# 04pwr_pmic.net
KiCad netlist of a schematic drawn in Altium Designer
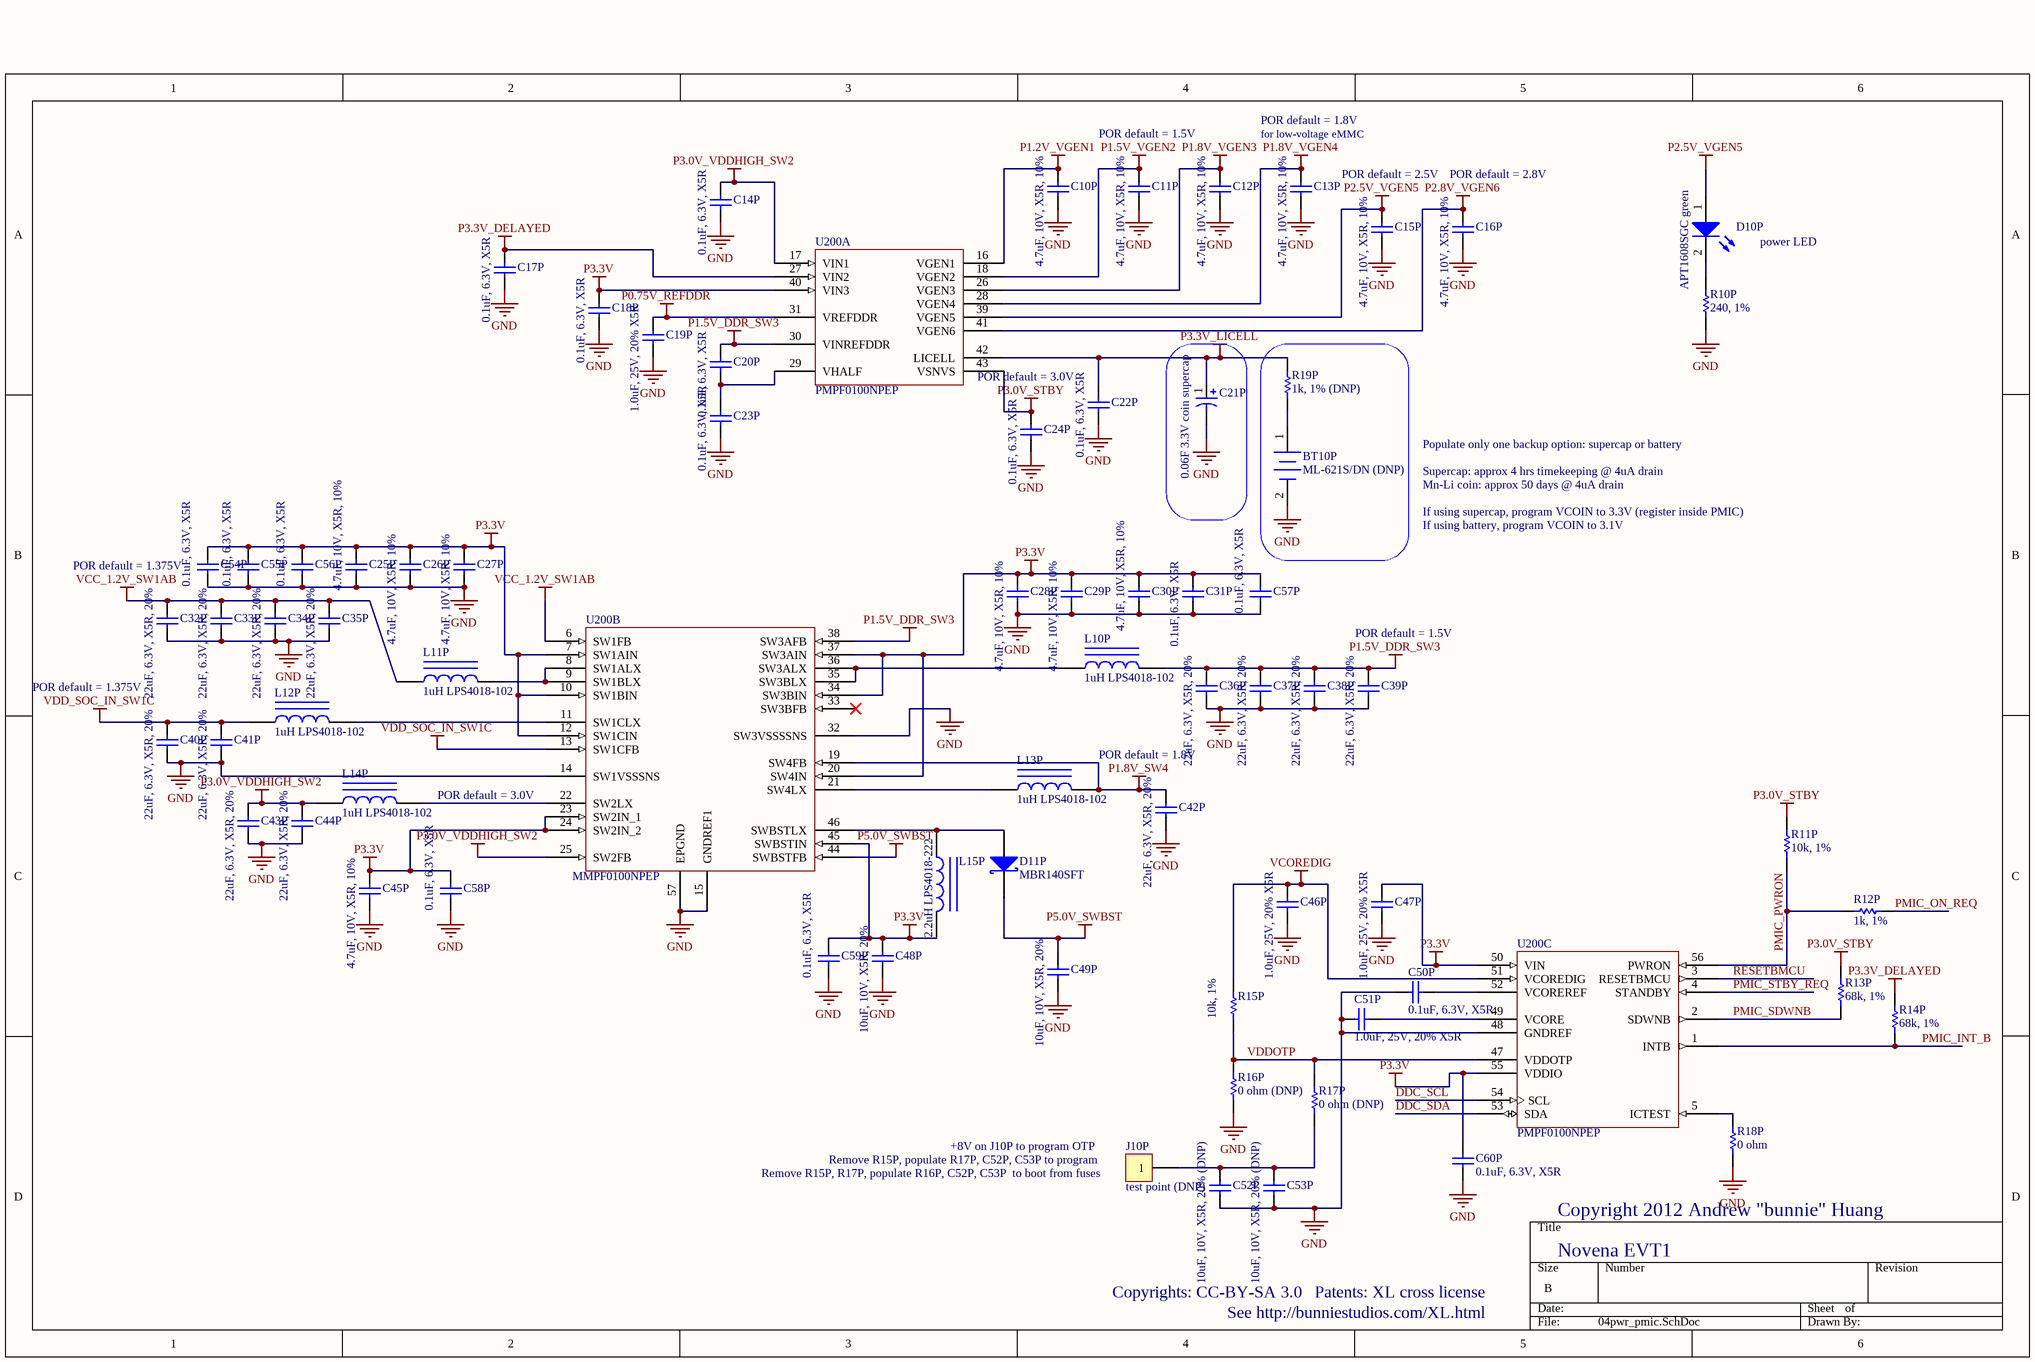
[diagram p0: 04pwr_pmic.SchDoc]

(export (version "E")
  (design (tool "Eeschema 10.0.6"))
  (components
    (comp (ref "BT10P")
      (value "ML-621S/DN (DNP)")
      (footprint "PAN_ML-621S-DN")
      (description "Panasonic Manganese Lithium Rechargeable battery")
      (fields (field (name "PUBLISHER") "Altium Limited"))
      (libsource (lib "Miscellaneous Devices") (part "Battery"))
    )
    (comp (ref "C10P")
      (value "4.7uF, 10V, X5R, 10%")
      (footprint "CAPC1608N_HD")
      (description "Capacitor (Semiconductor SIM Model)")
      (fields (field (name "PUBLISHER") "Altium Limited"))
      (libsource (lib "Miscellaneous Devices") (part "Cap Semi"))
    )
    (comp (ref "C11P")
      (value "4.7uF, 10V, X5R, 10%")
      (footprint "CAPC1608N_HD")
      (description "Capacitor (Semiconductor SIM Model)")
      (fields (field (name "PUBLISHER") "Altium Limited"))
      (libsource (lib "Miscellaneous Devices") (part "Cap Semi"))
    )
    (comp (ref "C12P")
      (value "4.7uF, 10V, X5R, 10%")
      (footprint "CAPC1608N_HD")
      (description "Capacitor (Semiconductor SIM Model)")
      (fields (field (name "PUBLISHER") "Altium Limited"))
      (libsource (lib "Miscellaneous Devices") (part "Cap Semi"))
    )
    (comp (ref "C13P")
      (value "4.7uF, 10V, X5R, 10%")
      (footprint "CAPC1608N_HD")
      (description "Capacitor (Semiconductor SIM Model)")
      (fields (field (name "PUBLISHER") "Altium Limited"))
      (libsource (lib "Miscellaneous Devices") (part "Cap Semi"))
    )
    (comp (ref "C14P")
      (value "0.1uF, 6.3V, X5R")
      (footprint "CAPC0603N_B")
      (description "Capacitor (Semiconductor SIM Model)")
      (fields (field (name "PUBLISHER") "Altium Limited"))
      (libsource (lib "Miscellaneous Devices") (part "Cap Semi"))
    )
    (comp (ref "C15P")
      (value "4.7uF, 10V, X5R, 10%")
      (footprint "CAPC1608N_HD")
      (description "Capacitor (Semiconductor SIM Model)")
      (fields (field (name "PUBLISHER") "Altium Limited"))
      (libsource (lib "Miscellaneous Devices") (part "Cap Semi"))
    )
    (comp (ref "C16P")
      (value "4.7uF, 10V, X5R, 10%")
      (footprint "CAPC1608N_HD")
      (description "Capacitor (Semiconductor SIM Model)")
      (fields (field (name "PUBLISHER") "Altium Limited"))
      (libsource (lib "Miscellaneous Devices") (part "Cap Semi"))
    )
    (comp (ref "C17P")
      (value "0.1uF, 6.3V, X5R")
      (footprint "CAPC0603N_B")
      (description "Capacitor (Semiconductor SIM Model)")
      (fields (field (name "PUBLISHER") "Altium Limited"))
      (libsource (lib "Miscellaneous Devices") (part "Cap Semi"))
    )
    (comp (ref "C18P")
      (value "0.1uF, 6.3V, X5R")
      (footprint "CAPC0603N_B")
      (description "Capacitor (Semiconductor SIM Model)")
      (fields (field (name "PUBLISHER") "Altium Limited"))
      (libsource (lib "Miscellaneous Devices") (part "Cap Semi"))
    )
    (comp (ref "C19P")
      (value "1.0uF, 25V, 20% X5R")
      (footprint "CAPC1608N_HD")
      (description "Capacitor (Semiconductor SIM Model)")
      (fields (field (name "PUBLISHER") "Altium Limited"))
      (libsource (lib "Miscellaneous Devices") (part "Cap Semi"))
    )
    (comp (ref "C20P")
      (value "0.1uF, 6.3V, X5R")
      (footprint "CAPC0603N_B")
      (description "Capacitor (Semiconductor SIM Model)")
      (fields (field (name "PUBLISHER") "Altium Limited"))
      (libsource (lib "Miscellaneous Devices") (part "Cap Semi"))
    )
    (comp (ref "C21P")
      (value "0.06F 3.3V coin supercap")
      (footprint "TAIYO_YUDEN_PAS414HR-VA5R")
      (description "Taiyo Yuden PAS414HR-VA5R")
      (fields (field (name "PUBLISHER") "Altium Limited"))
      (libsource (lib "Miscellaneous Devices") (part "Cap Pol3"))
    )
    (comp (ref "C22P")
      (value "0.1uF, 6.3V, X5R")
      (footprint "CAPC0603N_B")
      (description "Capacitor (Semiconductor SIM Model)")
      (fields (field (name "PUBLISHER") "Altium Limited"))
      (libsource (lib "Miscellaneous Devices") (part "Cap Semi"))
    )
    (comp (ref "C23P")
      (value "0.1uF, 6.3V, X5R")
      (footprint "CAPC0603N_B")
      (description "Capacitor (Semiconductor SIM Model)")
      (fields (field (name "PUBLISHER") "Altium Limited"))
      (libsource (lib "Miscellaneous Devices") (part "Cap Semi"))
    )
    (comp (ref "C24P")
      (value "0.1uF, 6.3V, X5R")
      (footprint "CAPC0603N_B")
      (description "Capacitor (Semiconductor SIM Model)")
      (fields (field (name "PUBLISHER") "Altium Limited"))
      (libsource (lib "Miscellaneous Devices") (part "Cap Semi"))
    )
    (comp (ref "C25P")
      (value "4.7uF, 10V, X5R, 10%")
      (footprint "CAPC1608N_HD")
      (description "Capacitor (Semiconductor SIM Model)")
      (fields (field (name "PUBLISHER") "Altium Limited"))
      (libsource (lib "Miscellaneous Devices") (part "Cap Semi"))
    )
    (comp (ref "C26P")
      (value "4.7uF, 10V, X5R, 10%")
      (footprint "CAPC1608N_HD")
      (description "Capacitor (Semiconductor SIM Model)")
      (fields (field (name "PUBLISHER") "Altium Limited"))
      (libsource (lib "Miscellaneous Devices") (part "Cap Semi"))
    )
    (comp (ref "C27P")
      (value "4.7uF, 10V, X5R, 10%")
      (footprint "CAPC1608N_HD")
      (description "Capacitor (Semiconductor SIM Model)")
      (fields (field (name "PUBLISHER") "Altium Limited"))
      (libsource (lib "Miscellaneous Devices") (part "Cap Semi"))
    )
    (comp (ref "C28P")
      (value "4.7uF, 10V, X5R, 10%")
      (footprint "CAPC1608N_HD")
      (description "Capacitor (Semiconductor SIM Model)")
      (fields (field (name "PUBLISHER") "Altium Limited"))
      (libsource (lib "Miscellaneous Devices") (part "Cap Semi"))
    )
    (comp (ref "C29P")
      (value "4.7uF, 10V, X5R, 10%")
      (footprint "CAPC1608N_HD")
      (description "Capacitor (Semiconductor SIM Model)")
      (fields (field (name "PUBLISHER") "Altium Limited"))
      (libsource (lib "Miscellaneous Devices") (part "Cap Semi"))
    )
    (comp (ref "C30P")
      (value "4.7uF, 10V, X5R, 10%")
      (footprint "CAPC1608N_HD")
      (description "Capacitor (Semiconductor SIM Model)")
      (fields (field (name "PUBLISHER") "Altium Limited"))
      (libsource (lib "Miscellaneous Devices") (part "Cap Semi"))
    )
    (comp (ref "C31P")
      (value "0.1uF, 6.3V, X5R")
      (footprint "CAPC0603N_B")
      (description "Capacitor (Semiconductor SIM Model)")
      (fields (field (name "PUBLISHER") "Altium Limited"))
      (libsource (lib "Miscellaneous Devices") (part "Cap Semi"))
    )
    (comp (ref "C32P")
      (value "22uF, 6.3V, X5R, 20%")
      (footprint "CAPC1608N_HD")
      (description "Capacitor (Semiconductor SIM Model)")
      (fields (field (name "PUBLISHER") "Altium Limited"))
      (libsource (lib "Miscellaneous Devices") (part "Cap Semi"))
    )
    (comp (ref "C33P")
      (value "22uF, 6.3V, X5R, 20%")
      (footprint "CAPC1608N_HD")
      (description "Capacitor (Semiconductor SIM Model)")
      (fields (field (name "PUBLISHER") "Altium Limited"))
      (libsource (lib "Miscellaneous Devices") (part "Cap Semi"))
    )
    (comp (ref "C34P")
      (value "22uF, 6.3V, X5R, 20%")
      (footprint "CAPC1608N_HD")
      (description "Capacitor (Semiconductor SIM Model)")
      (fields (field (name "PUBLISHER") "Altium Limited"))
      (libsource (lib "Miscellaneous Devices") (part "Cap Semi"))
    )
    (comp (ref "C35P")
      (value "22uF, 6.3V, X5R, 20%")
      (footprint "CAPC1608N_HD")
      (description "Capacitor (Semiconductor SIM Model)")
      (fields (field (name "PUBLISHER") "Altium Limited"))
      (libsource (lib "Miscellaneous Devices") (part "Cap Semi"))
    )
    (comp (ref "C36P")
      (value "22uF, 6.3V, X5R, 20%")
      (footprint "CAPC1608N_HD")
      (description "Capacitor (Semiconductor SIM Model)")
      (fields (field (name "PUBLISHER") "Altium Limited"))
      (libsource (lib "Miscellaneous Devices") (part "Cap Semi"))
    )
    (comp (ref "C37P")
      (value "22uF, 6.3V, X5R, 20%")
      (footprint "CAPC1608N_HD")
      (description "Capacitor (Semiconductor SIM Model)")
      (fields (field (name "PUBLISHER") "Altium Limited"))
      (libsource (lib "Miscellaneous Devices") (part "Cap Semi"))
    )
    (comp (ref "C38P")
      (value "22uF, 6.3V, X5R, 20%")
      (footprint "CAPC1608N_HD")
      (description "Capacitor (Semiconductor SIM Model)")
      (fields (field (name "PUBLISHER") "Altium Limited"))
      (libsource (lib "Miscellaneous Devices") (part "Cap Semi"))
    )
    (comp (ref "C39P")
      (value "22uF, 6.3V, X5R, 20%")
      (footprint "CAPC1608N_HD")
      (description "Capacitor (Semiconductor SIM Model)")
      (fields (field (name "PUBLISHER") "Altium Limited"))
      (libsource (lib "Miscellaneous Devices") (part "Cap Semi"))
    )
    (comp (ref "C40P")
      (value "22uF, 6.3V, X5R, 20%")
      (footprint "CAPC1608N_HD")
      (description "Capacitor (Semiconductor SIM Model)")
      (fields (field (name "PUBLISHER") "Altium Limited"))
      (libsource (lib "Miscellaneous Devices") (part "Cap Semi"))
    )
    (comp (ref "C41P")
      (value "22uF, 6.3V, X5R, 20%")
      (footprint "CAPC1608N_HD")
      (description "Capacitor (Semiconductor SIM Model)")
      (fields (field (name "PUBLISHER") "Altium Limited"))
      (libsource (lib "Miscellaneous Devices") (part "Cap Semi"))
    )
    (comp (ref "C42P")
      (value "22uF, 6.3V, X5R, 20%")
      (footprint "CAPC1608N_HD")
      (description "Capacitor (Semiconductor SIM Model)")
      (fields (field (name "PUBLISHER") "Altium Limited"))
      (libsource (lib "Miscellaneous Devices") (part "Cap Semi"))
    )
    (comp (ref "C43P")
      (value "22uF, 6.3V, X5R, 20%")
      (footprint "CAPC1608N_HD")
      (description "Capacitor (Semiconductor SIM Model)")
      (fields (field (name "PUBLISHER") "Altium Limited"))
      (libsource (lib "Miscellaneous Devices") (part "Cap Semi"))
    )
    (comp (ref "C44P")
      (value "22uF, 6.3V, X5R, 20%")
      (footprint "CAPC1608N_HD")
      (description "Capacitor (Semiconductor SIM Model)")
      (fields (field (name "PUBLISHER") "Altium Limited"))
      (libsource (lib "Miscellaneous Devices") (part "Cap Semi"))
    )
    (comp (ref "C45P")
      (value "4.7uF, 10V, X5R, 10%")
      (footprint "CAPC1608N_HD")
      (description "Capacitor (Semiconductor SIM Model)")
      (fields (field (name "PUBLISHER") "Altium Limited"))
      (libsource (lib "Miscellaneous Devices") (part "Cap Semi"))
    )
    (comp (ref "C46P")
      (value "1.0uF, 25V, 20% X5R")
      (footprint "CAPC1608N_HD")
      (description "Capacitor (Semiconductor SIM Model)")
      (fields (field (name "PUBLISHER") "Altium Limited"))
      (libsource (lib "Miscellaneous Devices") (part "Cap Semi"))
    )
    (comp (ref "C47P")
      (value "1.0uF, 25V, 20% X5R")
      (footprint "CAPC1608N_HD")
      (description "Capacitor (Semiconductor SIM Model)")
      (fields (field (name "PUBLISHER") "Altium Limited"))
      (libsource (lib "Miscellaneous Devices") (part "Cap Semi"))
    )
    (comp (ref "C48P")
      (value "10uF, 10V, X5R, 20%")
      (footprint "CAPC1608N")
      (description "Capacitor (Semiconductor SIM Model)")
      (fields (field (name "PUBLISHER") "Altium Limited"))
      (libsource (lib "Miscellaneous Devices") (part "Cap Semi"))
    )
    (comp (ref "C49P")
      (value "10uF, 10V, X5R, 20%")
      (footprint "CAPC1608N")
      (description "Capacitor (Semiconductor SIM Model)")
      (fields (field (name "PUBLISHER") "Altium Limited"))
      (libsource (lib "Miscellaneous Devices") (part "Cap Semi"))
    )
    (comp (ref "C50P")
      (value "0.1uF, 6.3V, X5R")
      (footprint "CAPC0603N_B")
      (description "Capacitor (Semiconductor SIM Model)")
      (fields (field (name "PUBLISHER") "Altium Limited"))
      (libsource (lib "Miscellaneous Devices") (part "Cap Semi"))
    )
    (comp (ref "C51P")
      (value "1.0uF, 25V, 20% X5R")
      (footprint "CAPC1608N_HD")
      (description "Capacitor (Semiconductor SIM Model)")
      (fields (field (name "PUBLISHER") "Altium Limited"))
      (libsource (lib "Miscellaneous Devices") (part "Cap Semi"))
    )
    (comp (ref "C52P")
      (value "10uF, 10V, X5R, 20% (DNP)")
      (footprint "CAPC1608N")
      (description "Capacitor (Semiconductor SIM Model)")
      (fields (field (name "PUBLISHER") "Altium Limited"))
      (libsource (lib "Miscellaneous Devices") (part "Cap Semi"))
    )
    (comp (ref "C53P")
      (value "10uF, 10V, X5R, 20% (DNP)")
      (footprint "CAPC1608N")
      (description "Capacitor (Semiconductor SIM Model)")
      (fields (field (name "PUBLISHER") "Altium Limited"))
      (libsource (lib "Miscellaneous Devices") (part "Cap Semi"))
    )
    (comp (ref "C54P")
      (value "0.1uF, 6.3V, X5R")
      (footprint "CAPC0603N_B")
      (description "Capacitor (Semiconductor SIM Model)")
      (fields (field (name "PUBLISHER") "Altium Limited"))
      (libsource (lib "Miscellaneous Devices") (part "Cap Semi"))
    )
    (comp (ref "C55P")
      (value "0.1uF, 6.3V, X5R")
      (footprint "CAPC0603N_B")
      (description "Capacitor (Semiconductor SIM Model)")
      (fields (field (name "PUBLISHER") "Altium Limited"))
      (libsource (lib "Miscellaneous Devices") (part "Cap Semi"))
    )
    (comp (ref "C56P")
      (value "0.1uF, 6.3V, X5R")
      (footprint "CAPC0603N_B")
      (description "Capacitor (Semiconductor SIM Model)")
      (fields (field (name "PUBLISHER") "Altium Limited"))
      (libsource (lib "Miscellaneous Devices") (part "Cap Semi"))
    )
    (comp (ref "C57P")
      (value "0.1uF, 6.3V, X5R")
      (footprint "CAPC0603N_B")
      (description "Capacitor (Semiconductor SIM Model)")
      (fields (field (name "PUBLISHER") "Altium Limited"))
      (libsource (lib "Miscellaneous Devices") (part "Cap Semi"))
    )
    (comp (ref "C58P")
      (value "0.1uF, 6.3V, X5R")
      (footprint "CAPC0603N_B")
      (description "Capacitor (Semiconductor SIM Model)")
      (fields (field (name "PUBLISHER") "Altium Limited"))
      (libsource (lib "Miscellaneous Devices") (part "Cap Semi"))
    )
    (comp (ref "C59P")
      (value "0.1uF, 6.3V, X5R")
      (footprint "CAPC0603N_B")
      (description "Capacitor (Semiconductor SIM Model)")
      (fields (field (name "PUBLISHER") "Altium Limited"))
      (libsource (lib "Miscellaneous Devices") (part "Cap Semi"))
    )
    (comp (ref "C60P")
      (value "0.1uF, 6.3V, X5R")
      (footprint "CAPC0603N_B")
      (description "Capacitor (Semiconductor SIM Model)")
      (fields (field (name "PUBLISHER") "Altium Limited"))
      (libsource (lib "Miscellaneous Devices") (part "Cap Semi"))
    )
    (comp (ref "D10P")
      (value "APT1608SGC green")
      (footprint "CD1608-0603")
      (description "Typical RED, GREEN, YELLOW, AMBER GaAs LED")
      (fields (field (name "PUBLISHER") "Altium Limited"))
      (libsource (lib "Miscellaneous Devices") (part "LED2"))
    )
    (comp (ref "D11P")
      (value "MBR140SFT")
      (footprint "SOD123")
      (description "Schottky Diode")
      (fields (field (name "PUBLISHER") "Altium Limited"))
      (libsource (lib "Miscellaneous Devices") (part "D Schottky"))
    )
    (comp (ref "J10P")
      (value "test point (DNP)")
      (footprint "TP_SMT_38mil")
      (description "Connector")
      (libsource (lib "*") (part "CON1"))
    )
    (comp (ref "L10P")
      (value "1uH LPS4018-102")
      (footprint "COILCRAFT_LPS4018")
      (description "Magnetic-Core Inductor")
      (fields (field (name "PUBLISHER") "Altium Limited"))
      (libsource (lib "Miscellaneous Devices") (part "Inductor Iron"))
    )
    (comp (ref "L11P")
      (value "1uH LPS4018-102")
      (footprint "COILCRAFT_LPS4018")
      (description "Magnetic-Core Inductor")
      (fields (field (name "PUBLISHER") "Altium Limited"))
      (libsource (lib "Miscellaneous Devices") (part "Inductor Iron"))
    )
    (comp (ref "L12P")
      (value "1uH LPS4018-102")
      (footprint "COILCRAFT_LPS4018")
      (description "Magnetic-Core Inductor")
      (fields (field (name "PUBLISHER") "Altium Limited"))
      (libsource (lib "Miscellaneous Devices") (part "Inductor Iron"))
    )
    (comp (ref "L13P")
      (value "1uH LPS4018-102")
      (footprint "COILCRAFT_LPS4018")
      (description "Magnetic-Core Inductor")
      (fields (field (name "PUBLISHER") "Altium Limited"))
      (libsource (lib "Miscellaneous Devices") (part "Inductor Iron"))
    )
    (comp (ref "L14P")
      (value "1uH LPS4018-102")
      (footprint "COILCRAFT_LPS4018")
      (description "Magnetic-Core Inductor")
      (fields (field (name "PUBLISHER") "Altium Limited"))
      (libsource (lib "Miscellaneous Devices") (part "Inductor Iron"))
    )
    (comp (ref "L15P")
      (value "2.2uH LPS4018-222")
      (footprint "COILCRAFT_LPS4018")
      (description "Magnetic-Core Inductor")
      (fields (field (name "PUBLISHER") "Altium Limited"))
      (libsource (lib "Miscellaneous Devices") (part "Inductor Iron"))
    )
    (comp (ref "R10P")
      (value "240, 1%")
      (footprint "RESC1005N")
      (description "Resistor")
      (fields (field (name "PUBLISHER") "Altium Limited"))
      (libsource (lib "Miscellaneous Devices") (part "Res1"))
    )
    (comp (ref "R11P")
      (value "10k, 1%")
      (footprint "RESC1005N")
      (description "Resistor")
      (fields (field (name "PUBLISHER") "Altium Limited"))
      (libsource (lib "Miscellaneous Devices") (part "Res1"))
    )
    (comp (ref "R12P")
      (value "1k, 1%")
      (footprint "RESC1005N")
      (description "Resistor")
      (fields (field (name "PUBLISHER") "Altium Limited"))
      (libsource (lib "Miscellaneous Devices") (part "Res1"))
    )
    (comp (ref "R13P")
      (value "68k, 1%")
      (footprint "RESC1005N")
      (description "Resistor")
      (fields (field (name "PUBLISHER") "Altium Limited"))
      (libsource (lib "Miscellaneous Devices") (part "Res1"))
    )
    (comp (ref "R14P")
      (value "68k, 1%")
      (footprint "RESC1005N")
      (description "Resistor")
      (fields (field (name "PUBLISHER") "Altium Limited"))
      (libsource (lib "Miscellaneous Devices") (part "Res1"))
    )
    (comp (ref "R15P")
      (value "10k, 1%")
      (footprint "RESC1005N")
      (description "Resistor")
      (fields (field (name "PUBLISHER") "Altium Limited"))
      (libsource (lib "Miscellaneous Devices") (part "Res1"))
    )
    (comp (ref "R16P")
      (value "0 ohm (DNP)")
      (footprint "RESC1005N")
      (description "Resistor")
      (fields (field (name "PUBLISHER") "Altium Limited"))
      (libsource (lib "Miscellaneous Devices") (part "Res1"))
    )
    (comp (ref "R17P")
      (value "0 ohm (DNP)")
      (footprint "RESC1005N")
      (description "Resistor")
      (fields (field (name "PUBLISHER") "Altium Limited"))
      (libsource (lib "Miscellaneous Devices") (part "Res1"))
    )
    (comp (ref "R18P")
      (value "0 ohm")
      (footprint "RESC1005N")
      (description "Resistor")
      (fields (field (name "PUBLISHER") "Altium Limited"))
      (libsource (lib "Miscellaneous Devices") (part "Res1"))
    )
    (comp (ref "R19P")
      (value "1k, 1% (DNP)")
      (footprint "RESC1005N")
      (description "Resistor")
      (fields (field (name "PUBLISHER") "Altium Limited"))
      (libsource (lib "Miscellaneous Devices") (part "Res1"))
    )
    (comp (ref "U200")
      (value "PMPF0100NPEP")
      (footprint "FREESCALE_QFN50P800X800X90-56N")
      (description "PMIC for i.MX6 series")
      (libsource (lib "commonsch") (part "PMPF0100NPEP"))
    )
  )
  (nets
    (net (code "1") (name "/DDC_SCL") (class "Default")
      (node (ref "U200") (pin "54") (pinfunction "SCL_54") (pintype "input"))
    )
    (net (code "2") (name "/DDC_SDA") (class "Default")
      (node (ref "U200") (pin "53") (pinfunction "SDA_53") (pintype "bidirectional"))
    )
    (net (code "3") (name "/PMIC_INT_B") (class "Default")
      (node (ref "R14P") (pin "1") (pinfunction "1_1") (pintype "passive"))
      (node (ref "U200") (pin "1") (pinfunction "INTB_1") (pintype "output"))
    )
    (net (code "4") (name "/PMIC_ON_REQ") (class "Default")
      (node (ref "R12P") (pin "2") (pinfunction "2_2") (pintype "passive"))
    )
    (net (code "5") (name "/PMIC_PWRON") (class "Default")
      (node (ref "R11P") (pin "1") (pinfunction "1_1") (pintype "passive"))
      (node (ref "R12P") (pin "1") (pinfunction "1_1") (pintype "passive"))
      (node (ref "U200") (pin "56") (pinfunction "PWRON_56") (pintype "input"))
    )
    (net (code "6") (name "/PMIC_SDWNB") (class "Default")
      (node (ref "R13P") (pin "1") (pinfunction "1_1") (pintype "passive"))
      (node (ref "U200") (pin "2") (pinfunction "SDWNB_2") (pintype "output"))
    )
    (net (code "7") (name "/PMIC_STBY_REQ") (class "Default")
      (node (ref "U200") (pin "4") (pinfunction "STANDBY_4") (pintype "input"))
    )
    (net (code "8") (name "/RESETBMCU") (class "Default")
      (node (ref "U200") (pin "3") (pinfunction "RESETBMCU_3") (pintype "output"))
    )
    (net (code "9") (name "/VDDOTP") (class "Default")
      (node (ref "R15P") (pin "1") (pinfunction "1_1") (pintype "passive"))
      (node (ref "R16P") (pin "2") (pinfunction "2_2") (pintype "passive"))
      (node (ref "R17P") (pin "2") (pinfunction "2_2") (pintype "passive"))
      (node (ref "U200") (pin "47") (pinfunction "VDDOTP_47") (pintype "passive"))
    )
    (net (code "10") (name "GND") (class "Default")
      (node (ref "BT10P") (pin "2") (pinfunction "-_2") (pintype "passive"))
      (node (ref "C10P") (pin "2") (pinfunction "2_2") (pintype "passive"))
      (node (ref "C11P") (pin "2") (pinfunction "2_2") (pintype "passive"))
      (node (ref "C12P") (pin "2") (pinfunction "2_2") (pintype "passive"))
      (node (ref "C13P") (pin "2") (pinfunction "2_2") (pintype "passive"))
      (node (ref "C14P") (pin "2") (pinfunction "2_2") (pintype "passive"))
      (node (ref "C15P") (pin "2") (pinfunction "2_2") (pintype "passive"))
      (node (ref "C16P") (pin "2") (pinfunction "2_2") (pintype "passive"))
      (node (ref "C17P") (pin "2") (pinfunction "2_2") (pintype "passive"))
      (node (ref "C18P") (pin "2") (pinfunction "2_2") (pintype "passive"))
      (node (ref "C19P") (pin "2") (pinfunction "2_2") (pintype "passive"))
      (node (ref "C21P") (pin "2") (pinfunction "2_2") (pintype "passive"))
      (node (ref "C22P") (pin "2") (pinfunction "2_2") (pintype "passive"))
      (node (ref "C23P") (pin "2") (pinfunction "2_2") (pintype "passive"))
      (node (ref "C24P") (pin "2") (pinfunction "2_2") (pintype "passive"))
      (node (ref "C25P") (pin "2") (pinfunction "2_2") (pintype "passive"))
      (node (ref "C26P") (pin "2") (pinfunction "2_2") (pintype "passive"))
      (node (ref "C27P") (pin "2") (pinfunction "2_2") (pintype "passive"))
      (node (ref "C28P") (pin "2") (pinfunction "2_2") (pintype "passive"))
      (node (ref "C29P") (pin "2") (pinfunction "2_2") (pintype "passive"))
      (node (ref "C30P") (pin "2") (pinfunction "2_2") (pintype "passive"))
      (node (ref "C31P") (pin "2") (pinfunction "2_2") (pintype "passive"))
      (node (ref "C32P") (pin "2") (pinfunction "2_2") (pintype "passive"))
      (node (ref "C33P") (pin "2") (pinfunction "2_2") (pintype "passive"))
      (node (ref "C34P") (pin "2") (pinfunction "2_2") (pintype "passive"))
      (node (ref "C35P") (pin "2") (pinfunction "2_2") (pintype "passive"))
      (node (ref "C36P") (pin "2") (pinfunction "2_2") (pintype "passive"))
      (node (ref "C37P") (pin "2") (pinfunction "2_2") (pintype "passive"))
      (node (ref "C38P") (pin "2") (pinfunction "2_2") (pintype "passive"))
      (node (ref "C39P") (pin "2") (pinfunction "2_2") (pintype "passive"))
      (node (ref "C40P") (pin "2") (pinfunction "2_2") (pintype "passive"))
      (node (ref "C41P") (pin "2") (pinfunction "2_2") (pintype "passive"))
      (node (ref "C42P") (pin "2") (pinfunction "2_2") (pintype "passive"))
      (node (ref "C43P") (pin "2") (pinfunction "2_2") (pintype "passive"))
      (node (ref "C44P") (pin "2") (pinfunction "2_2") (pintype "passive"))
      (node (ref "C45P") (pin "2") (pinfunction "2_2") (pintype "passive"))
      (node (ref "C46P") (pin "2") (pinfunction "2_2") (pintype "passive"))
      (node (ref "C47P") (pin "2") (pinfunction "2_2") (pintype "passive"))
      (node (ref "C48P") (pin "2") (pinfunction "2_2") (pintype "passive"))
      (node (ref "C49P") (pin "2") (pinfunction "2_2") (pintype "passive"))
      (node (ref "C50P") (pin "2") (pinfunction "2_2") (pintype "passive"))
      (node (ref "C51P") (pin "2") (pinfunction "2_2") (pintype "passive"))
      (node (ref "C52P") (pin "2") (pinfunction "2_2") (pintype "passive"))
      (node (ref "C53P") (pin "2") (pinfunction "2_2") (pintype "passive"))
      (node (ref "C54P") (pin "2") (pinfunction "2_2") (pintype "passive"))
      (node (ref "C55P") (pin "2") (pinfunction "2_2") (pintype "passive"))
      (node (ref "C56P") (pin "2") (pinfunction "2_2") (pintype "passive"))
      (node (ref "C57P") (pin "2") (pinfunction "2_2") (pintype "passive"))
      (node (ref "C58P") (pin "2") (pinfunction "2_2") (pintype "passive"))
      (node (ref "C59P") (pin "2") (pinfunction "2_2") (pintype "passive"))
      (node (ref "C60P") (pin "1") (pinfunction "1_1") (pintype "passive"))
      (node (ref "R10P") (pin "1") (pinfunction "1_1") (pintype "passive"))
      (node (ref "R16P") (pin "1") (pinfunction "1_1") (pintype "passive"))
      (node (ref "R18P") (pin "1") (pinfunction "1_1") (pintype "passive"))
      (node (ref "U200") (pin "14") (pinfunction "SW1VSSSNS_14") (pintype "power_in"))
      (node (ref "U200") (pin "15") (pinfunction "GNDREF1_15") (pintype "power_in"))
      (node (ref "U200") (pin "32") (pinfunction "SW3VSSSSNS_32") (pintype "power_in"))
      (node (ref "U200") (pin "48") (pinfunction "GNDREF_48") (pintype "power_in"))
      (node (ref "U200") (pin "57") (pinfunction "EPGND_57") (pintype "power_in"))
    )
    (net (code "11") (name "Net-(BT10P-+)") (class "Default")
      (node (ref "BT10P") (pin "1") (pinfunction "+_1") (pintype "passive"))
      (node (ref "R19P") (pin "1") (pinfunction "1_1") (pintype "passive"))
    )
    (net (code "12") (name "Net-(C52P-Pad1)") (class "Default")
      (node (ref "C52P") (pin "1") (pinfunction "1_1") (pintype "passive"))
      (node (ref "C53P") (pin "1") (pinfunction "1_1") (pintype "passive"))
      (node (ref "J10P") (pin "1") (pinfunction "1_1") (pintype "passive"))
      (node (ref "R17P") (pin "1") (pinfunction "1_1") (pintype "passive"))
    )
    (net (code "13") (name "Net-(D10P-K)") (class "Default")
      (node (ref "D10P") (pin "2") (pinfunction "K_2") (pintype "passive"))
      (node (ref "R10P") (pin "2") (pinfunction "2_2") (pintype "passive"))
    )
    (net (code "14") (name "Net-(D11P-A)") (class "Default")
      (node (ref "D11P") (pin "1") (pinfunction "A_1") (pintype "passive"))
      (node (ref "L15P") (pin "1") (pinfunction "1_1") (pintype "passive"))
      (node (ref "U200") (pin "46") (pinfunction "SWBSTLX_46") (pintype "passive"))
    )
    (net (code "15") (name "Net-(U200A-VHALF)") (class "Default")
      (node (ref "C20P") (pin "2") (pinfunction "2_2") (pintype "passive"))
      (node (ref "C23P") (pin "1") (pinfunction "1_1") (pintype "passive"))
      (node (ref "U200") (pin "29") (pinfunction "VHALF_29") (pintype "passive"))
    )
    (net (code "16") (name "Net-(U200B-SW1ALX)") (class "Default")
      (node (ref "L11P") (pin "2") (pinfunction "2_2") (pintype "passive"))
      (node (ref "U200") (pin "8") (pinfunction "SW1ALX_8") (pintype "passive"))
      (node (ref "U200") (pin "9") (pinfunction "SW1BLX_9") (pintype "passive"))
    )
    (net (code "17") (name "Net-(U200B-SW1CLX)") (class "Default")
      (node (ref "L12P") (pin "2") (pinfunction "2_2") (pintype "passive"))
      (node (ref "U200") (pin "11") (pinfunction "SW1CLX_11") (pintype "passive"))
    )
    (net (code "18") (name "Net-(U200B-SW2LX)") (class "Default")
      (node (ref "L14P") (pin "2") (pinfunction "2_2") (pintype "passive"))
      (node (ref "U200") (pin "22") (pinfunction "SW2LX_22") (pintype "passive"))
    )
    (net (code "19") (name "Net-(U200B-SW3ALX)") (class "Default")
      (node (ref "L10P") (pin "1") (pinfunction "1_1") (pintype "passive"))
      (node (ref "U200") (pin "35") (pinfunction "SW3BLX_35") (pintype "passive"))
      (node (ref "U200") (pin "36") (pinfunction "SW3ALX_36") (pintype "passive"))
    )
    (net (code "20") (name "Net-(U200B-SW4LX)") (class "Default")
      (node (ref "L13P") (pin "1") (pinfunction "1_1") (pintype "passive"))
      (node (ref "U200") (pin "21") (pinfunction "SW4LX_21") (pintype "passive"))
    )
    (net (code "21") (name "Net-(U200C-ICTEST)") (class "Default")
      (node (ref "R18P") (pin "2") (pinfunction "2_2") (pintype "passive"))
      (node (ref "U200") (pin "5") (pinfunction "ICTEST_5") (pintype "input"))
    )
    (net (code "22") (name "Net-(U200C-VCORE)") (class "Default")
      (node (ref "C51P") (pin "1") (pinfunction "1_1") (pintype "passive"))
      (node (ref "U200") (pin "49") (pinfunction "VCORE_49") (pintype "passive"))
    )
    (net (code "23") (name "Net-(U200C-VCOREREF)") (class "Default")
      (node (ref "C50P") (pin "1") (pinfunction "1_1") (pintype "passive"))
      (node (ref "U200") (pin "52") (pinfunction "VCOREREF_52") (pintype "passive"))
    )
    (net (code "24") (name "P0.75V_REFDDR") (class "Default")
      (node (ref "C19P") (pin "1") (pinfunction "1_1") (pintype "passive"))
      (node (ref "U200") (pin "31") (pinfunction "VREFDDR_31") (pintype "power_in"))
    )
    (net (code "25") (name "P1.2V_VGEN1") (class "Default")
      (node (ref "C10P") (pin "1") (pinfunction "1_1") (pintype "passive"))
      (node (ref "U200") (pin "16") (pinfunction "VGEN1_16") (pintype "power_in"))
    )
    (net (code "26") (name "P1.5V_DDR_SW3") (class "Default")
      (node (ref "C20P") (pin "1") (pinfunction "1_1") (pintype "passive"))
      (node (ref "C36P") (pin "1") (pinfunction "1_1") (pintype "passive"))
      (node (ref "C37P") (pin "1") (pinfunction "1_1") (pintype "passive"))
      (node (ref "C38P") (pin "1") (pinfunction "1_1") (pintype "passive"))
      (node (ref "C39P") (pin "1") (pinfunction "1_1") (pintype "passive"))
      (node (ref "L10P") (pin "2") (pinfunction "2_2") (pintype "passive"))
      (node (ref "U200") (pin "30") (pinfunction "VINREFDDR_30") (pintype "power_in"))
      (node (ref "U200") (pin "38") (pinfunction "SW3AFB_38") (pintype "input"))
    )
    (net (code "27") (name "P1.5V_VGEN2") (class "Default")
      (node (ref "C11P") (pin "1") (pinfunction "1_1") (pintype "passive"))
      (node (ref "U200") (pin "18") (pinfunction "VGEN2_18") (pintype "power_in"))
    )
    (net (code "28") (name "P1.8V_SW4") (class "Default")
      (node (ref "C42P") (pin "1") (pinfunction "1_1") (pintype "passive"))
      (node (ref "L13P") (pin "2") (pinfunction "2_2") (pintype "passive"))
      (node (ref "U200") (pin "19") (pinfunction "SW4FB_19") (pintype "input"))
    )
    (net (code "29") (name "P1.8V_VGEN3") (class "Default")
      (node (ref "C12P") (pin "1") (pinfunction "1_1") (pintype "passive"))
      (node (ref "U200") (pin "26") (pinfunction "VGEN3_26") (pintype "power_in"))
    )
    (net (code "30") (name "P1.8V_VGEN4") (class "Default")
      (node (ref "C13P") (pin "1") (pinfunction "1_1") (pintype "passive"))
      (node (ref "U200") (pin "28") (pinfunction "VGEN4_28") (pintype "power_in"))
    )
    (net (code "31") (name "P2.5V_VGEN5") (class "Default")
      (node (ref "C15P") (pin "1") (pinfunction "1_1") (pintype "passive"))
      (node (ref "D10P") (pin "1") (pinfunction "A_1") (pintype "passive"))
      (node (ref "U200") (pin "39") (pinfunction "VGEN5_39") (pintype "power_in"))
    )
    (net (code "32") (name "P2.8V_VGEN6") (class "Default")
      (node (ref "C16P") (pin "1") (pinfunction "1_1") (pintype "passive"))
      (node (ref "U200") (pin "41") (pinfunction "VGEN6_41") (pintype "power_in"))
    )
    (net (code "33") (name "P3.0V_STBY") (class "Default")
      (node (ref "C24P") (pin "1") (pinfunction "1_1") (pintype "passive"))
      (node (ref "R11P") (pin "2") (pinfunction "2_2") (pintype "passive"))
      (node (ref "R13P") (pin "2") (pinfunction "2_2") (pintype "passive"))
      (node (ref "U200") (pin "43") (pinfunction "VSNVS_43") (pintype "power_in"))
    )
    (net (code "34") (name "P3.0V_VDDHIGH_SW2") (class "Default")
      (node (ref "C14P") (pin "1") (pinfunction "1_1") (pintype "passive"))
      (node (ref "C43P") (pin "1") (pinfunction "1_1") (pintype "passive"))
      (node (ref "C44P") (pin "1") (pinfunction "1_1") (pintype "passive"))
      (node (ref "L14P") (pin "1") (pinfunction "1_1") (pintype "passive"))
      (node (ref "U200") (pin "17") (pinfunction "VIN1_17") (pintype "input"))
      (node (ref "U200") (pin "25") (pinfunction "SW2FB_25") (pintype "input"))
    )
    (net (code "35") (name "P3.3V") (class "Default")
      (node (ref "C18P") (pin "1") (pinfunction "1_1") (pintype "passive"))
      (node (ref "C25P") (pin "1") (pinfunction "1_1") (pintype "passive"))
      (node (ref "C26P") (pin "1") (pinfunction "1_1") (pintype "passive"))
      (node (ref "C27P") (pin "1") (pinfunction "1_1") (pintype "passive"))
      (node (ref "C28P") (pin "1") (pinfunction "1_1") (pintype "passive"))
      (node (ref "C29P") (pin "1") (pinfunction "1_1") (pintype "passive"))
      (node (ref "C30P") (pin "1") (pinfunction "1_1") (pintype "passive"))
      (node (ref "C31P") (pin "1") (pinfunction "1_1") (pintype "passive"))
      (node (ref "C45P") (pin "1") (pinfunction "1_1") (pintype "passive"))
      (node (ref "C47P") (pin "1") (pinfunction "1_1") (pintype "passive"))
      (node (ref "C48P") (pin "1") (pinfunction "1_1") (pintype "passive"))
      (node (ref "C54P") (pin "1") (pinfunction "1_1") (pintype "passive"))
      (node (ref "C55P") (pin "1") (pinfunction "1_1") (pintype "passive"))
      (node (ref "C56P") (pin "1") (pinfunction "1_1") (pintype "passive"))
      (node (ref "C57P") (pin "1") (pinfunction "1_1") (pintype "passive"))
      (node (ref "C58P") (pin "1") (pinfunction "1_1") (pintype "passive"))
      (node (ref "C59P") (pin "1") (pinfunction "1_1") (pintype "passive"))
      (node (ref "C60P") (pin "2") (pinfunction "2_2") (pintype "passive"))
      (node (ref "L15P") (pin "2") (pinfunction "2_2") (pintype "passive"))
      (node (ref "U200") (pin "10") (pinfunction "SW1BIN_10") (pintype "input"))
      (node (ref "U200") (pin "12") (pinfunction "SW1CIN_12") (pintype "input"))
      (node (ref "U200") (pin "20") (pinfunction "SW4IN_20") (pintype "input"))
      (node (ref "U200") (pin "23") (pinfunction "SW2IN_1_23") (pintype "input"))
      (node (ref "U200") (pin "24") (pinfunction "SW2IN_2_24") (pintype "input"))
      (node (ref "U200") (pin "34") (pinfunction "SW3BIN_34") (pintype "input"))
      (node (ref "U200") (pin "37") (pinfunction "SW3AIN_37") (pintype "input"))
      (node (ref "U200") (pin "40") (pinfunction "VIN3_40") (pintype "input"))
      (node (ref "U200") (pin "45") (pinfunction "SWBSTIN_45") (pintype "input"))
      (node (ref "U200") (pin "50") (pinfunction "VIN_50") (pintype "input"))
      (node (ref "U200") (pin "55") (pinfunction "VDDIO_55") (pintype "power_in"))
      (node (ref "U200") (pin "7") (pinfunction "SW1AIN_7") (pintype "input"))
    )
    (net (code "36") (name "P3.3V_DELAYED") (class "Default")
      (node (ref "C17P") (pin "1") (pinfunction "1_1") (pintype "passive"))
      (node (ref "R14P") (pin "2") (pinfunction "2_2") (pintype "passive"))
      (node (ref "U200") (pin "27") (pinfunction "VIN2_27") (pintype "input"))
    )
    (net (code "37") (name "P3.3V_LICELL") (class "Default")
      (node (ref "C21P") (pin "1") (pinfunction "1_1") (pintype "passive"))
      (node (ref "C22P") (pin "1") (pinfunction "1_1") (pintype "passive"))
      (node (ref "R19P") (pin "2") (pinfunction "2_2") (pintype "passive"))
      (node (ref "U200") (pin "42") (pinfunction "LICELL_42") (pintype "power_in"))
    )
    (net (code "38") (name "P5.0V_SWBST") (class "Default")
      (node (ref "C49P") (pin "1") (pinfunction "1_1") (pintype "passive"))
      (node (ref "D11P") (pin "2") (pinfunction "K_2") (pintype "passive"))
      (node (ref "U200") (pin "44") (pinfunction "SWBSTFB_44") (pintype "input"))
    )
    (net (code "39") (name "VCC_1.2V_SW1AB") (class "Default")
      (node (ref "C32P") (pin "1") (pinfunction "1_1") (pintype "passive"))
      (node (ref "C33P") (pin "1") (pinfunction "1_1") (pintype "passive"))
      (node (ref "C34P") (pin "1") (pinfunction "1_1") (pintype "passive"))
      (node (ref "C35P") (pin "1") (pinfunction "1_1") (pintype "passive"))
      (node (ref "L11P") (pin "1") (pinfunction "1_1") (pintype "passive"))
      (node (ref "U200") (pin "6") (pinfunction "SW1FB_6") (pintype "input"))
    )
    (net (code "40") (name "VCOREDIG") (class "Default")
      (node (ref "C46P") (pin "1") (pinfunction "1_1") (pintype "passive"))
      (node (ref "R15P") (pin "2") (pinfunction "2_2") (pintype "passive"))
      (node (ref "U200") (pin "51") (pinfunction "VCOREDIG_51") (pintype "input"))
    )
    (net (code "41") (name "VDD_SOC_IN_SW1C") (class "Default")
      (node (ref "C40P") (pin "1") (pinfunction "1_1") (pintype "passive"))
      (node (ref "C41P") (pin "1") (pinfunction "1_1") (pintype "passive"))
      (node (ref "L12P") (pin "1") (pinfunction "1_1") (pintype "passive"))
      (node (ref "U200") (pin "13") (pinfunction "SW1CFB_13") (pintype "input"))
    )
    (net (code "42") (name "unconnected-(U200B-SW3BFB-Pad33)") (class "Default")
      (node (ref "U200") (pin "33") (pinfunction "SW3BFB_33") (pintype "input+no_connect"))
    )
  )
)
